# GR_Alim.net
KiCad netlist of a schematic drawn in Altium Designer
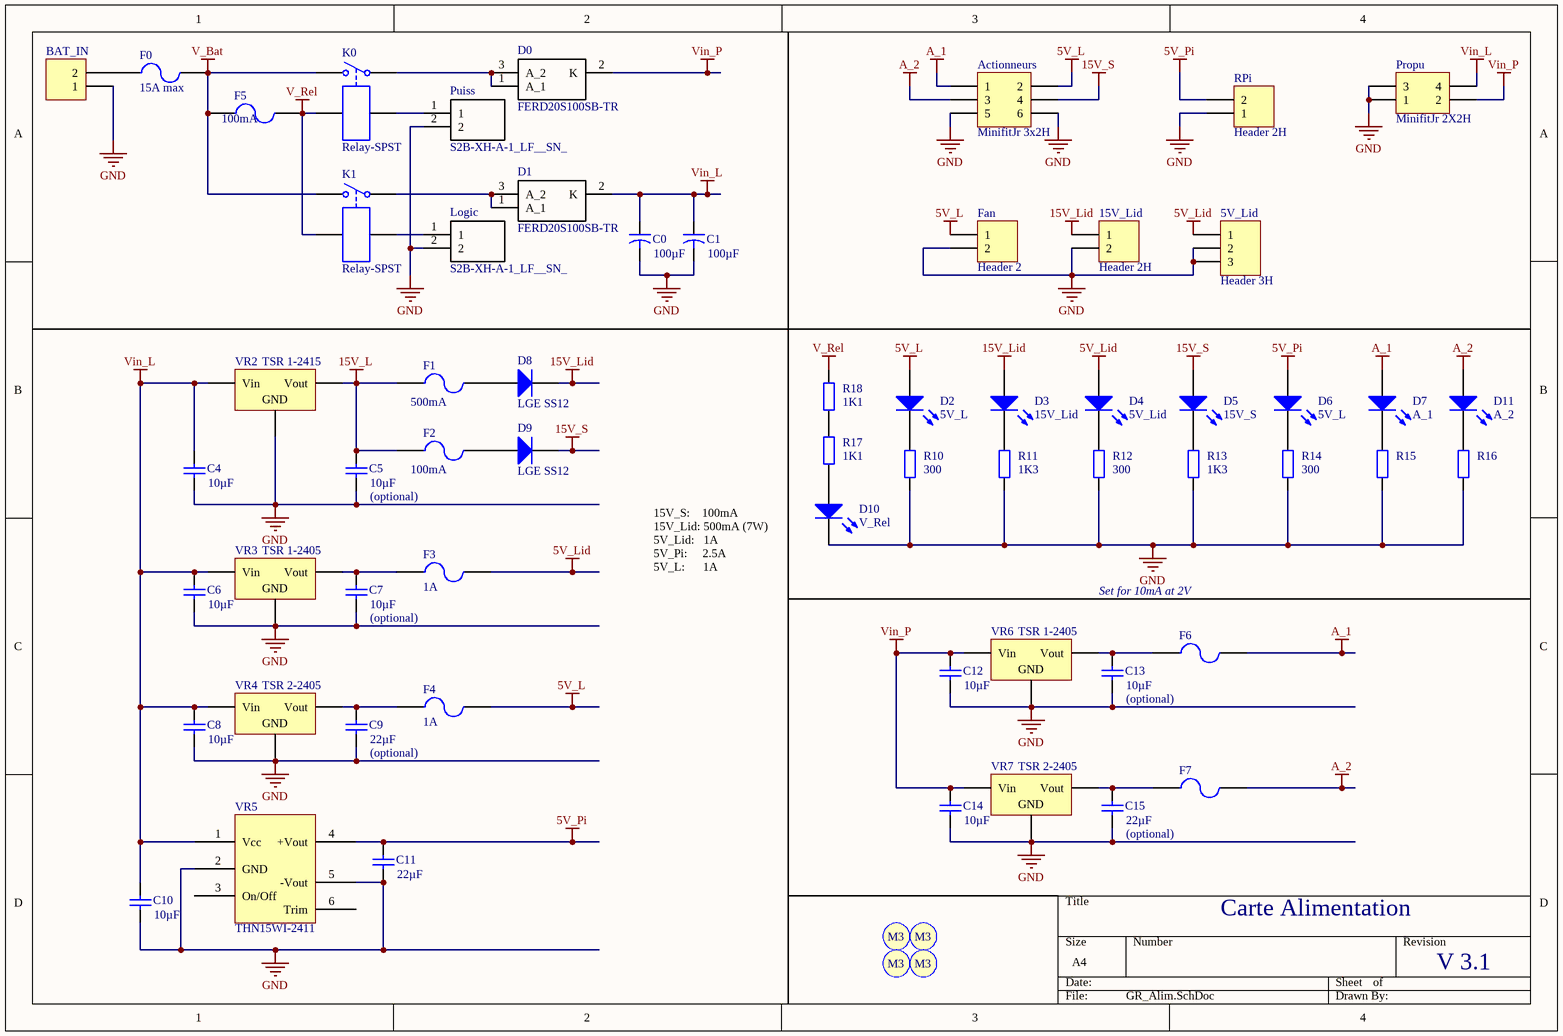
[diagram p0: GR_Alim.SchDoc]

(export (version "E")
  (design (tool "Eeschema 10.0.6"))
  (components
    (comp (ref "5V_Lid")
      (value "Header 3H")
      (footprint "S3B-XH-A")
      (description "Header, 3-Pin, Right Angle")
      (fields (field (name "PUBLISHER") "Altium Limited"))
      (libsource (lib "Miscellaneous Connectors") (part "Header 3H"))
    )
    (comp (ref "15V_Lid")
      (value "Header 2H")
      (footprint "S2B-XH-A")
      (description "Header, 2-Pin, Right Angle")
      (fields (field (name "PUBLISHER") "Altium Limited"))
      (libsource (lib "Miscellaneous Connectors") (part "Header 2H"))
    )
    (comp (ref "Actionneurs")
      (value "MinifitJr 3x2H")
      (footprint "MOLEX_MINIFITJR_3X2H")
      (description "Header, 3-Pin, Dual row, Right Angle")
      (fields (field (name "PUBLISHER") "Altium Limited"))
      (libsource (lib "Miscellaneous Connectors") (part "Header 3X2H"))
    )
    (comp (ref "BAT_IN")
      (value "Battery Onboard Solder")
      (footprint "Battery SALE")
      (description "Header, 2-Pin")
      (fields (field (name "PUBLISHER") "Altium Limited"))
      (libsource (lib "Miscellaneous Connectors") (part "Header 2"))
    )
    (comp (ref "C0")
      (value "100µF")
      (footprint "Condensateur")
      (description "Capacitor")
      (fields (field (name "Comment") "Cap2") (field (name "PUBLISHER") "Altium Limited"))
      (libsource (lib "Miscellaneous Devices") (part "Cap2"))
    )
    (comp (ref "C1")
      (value "100µF")
      (footprint "Condensateur")
      (description "Capacitor")
      (fields (field (name "Comment") "Cap2") (field (name "PUBLISHER") "Altium Limited"))
      (libsource (lib "Miscellaneous Devices") (part "Cap2"))
    )
    (comp (ref "C4")
      (value "10µF")
      (footprint "Capacitor 1206")
      (description "Capacitor")
      (fields (field (name "Comment") "Cap") (field (name "PUBLISHER") "Altium Limited"))
      (libsource (lib "Miscellaneous Devices") (part "Cap"))
    )
    (comp (ref "C5")
      (value "(optional)")
      (footprint "Capacitor 1206")
      (description "Capacitor")
      (fields (field (name "ALTIUM_VALUE") "10µF") (field (name "PUBLISHER") "Altium Limited"))
      (libsource (lib "Miscellaneous Devices") (part "Cap"))
    )
    (comp (ref "C6")
      (value "10µF")
      (footprint "Capacitor 1206")
      (description "Capacitor")
      (fields (field (name "Comment") "Cap") (field (name "PUBLISHER") "Altium Limited"))
      (libsource (lib "Miscellaneous Devices") (part "Cap"))
    )
    (comp (ref "C7")
      (value "(optional)")
      (footprint "Capacitor 1206")
      (description "Capacitor")
      (fields (field (name "ALTIUM_VALUE") "10µF") (field (name "PUBLISHER") "Altium Limited"))
      (libsource (lib "Miscellaneous Devices") (part "Cap"))
    )
    (comp (ref "C8")
      (value "10µF")
      (footprint "Capacitor 1206")
      (description "Capacitor")
      (fields (field (name "Comment") "Cap") (field (name "PUBLISHER") "Altium Limited"))
      (libsource (lib "Miscellaneous Devices") (part "Cap"))
    )
    (comp (ref "C9")
      (value "(optional)")
      (footprint "Capacitor 1206")
      (description "Capacitor")
      (fields (field (name "ALTIUM_VALUE") "22µF") (field (name "PUBLISHER") "Altium Limited"))
      (libsource (lib "Miscellaneous Devices") (part "Cap"))
    )
    (comp (ref "C10")
      (value "10µF")
      (footprint "Capacitor 1206")
      (description "Capacitor")
      (fields (field (name "Comment") "Cap") (field (name "PUBLISHER") "Altium Limited"))
      (libsource (lib "Miscellaneous Devices") (part "Cap"))
    )
    (comp (ref "C11")
      (value "22µF")
      (footprint "Capacitor 1206")
      (description "Capacitor")
      (fields (field (name "Comment") "Cap") (field (name "PUBLISHER") "Altium Limited"))
      (libsource (lib "Miscellaneous Devices") (part "Cap"))
    )
    (comp (ref "C12")
      (value "10µF")
      (footprint "Capacitor 1206")
      (description "Capacitor")
      (fields (field (name "Comment") "Cap") (field (name "PUBLISHER") "Altium Limited"))
      (libsource (lib "Miscellaneous Devices") (part "Cap"))
    )
    (comp (ref "C13")
      (value "(optional)")
      (footprint "Capacitor 1206")
      (description "Capacitor")
      (fields (field (name "ALTIUM_VALUE") "10µF") (field (name "PUBLISHER") "Altium Limited"))
      (libsource (lib "Miscellaneous Devices") (part "Cap"))
    )
    (comp (ref "C14")
      (value "10µF")
      (footprint "Capacitor 1206")
      (description "Capacitor")
      (fields (field (name "Comment") "Cap") (field (name "PUBLISHER") "Altium Limited"))
      (libsource (lib "Miscellaneous Devices") (part "Cap"))
    )
    (comp (ref "C15")
      (value "(optional)")
      (footprint "Capacitor 1206")
      (description "Capacitor")
      (fields (field (name "ALTIUM_VALUE") "22µF") (field (name "PUBLISHER") "Altium Limited"))
      (libsource (lib "Miscellaneous Devices") (part "Cap"))
    )
    (comp (ref "D0")
      (value "FERD20S100SB-TR")
      (footprint "SamacSys:FERD20H100SBTR")
      (description "Diode")
      (fields (field (name "MOUSER PART NUMBER") "511-FERD20S100SB-TR"))
      (libsource (lib "*") (part "FERD20S100SB-TR"))
    )
    (comp (ref "D1")
      (value "FERD20S100SB-TR")
      (footprint "SamacSys:FERD20H100SBTR")
      (description "Diode")
      (fields (field (name "MOUSER PART NUMBER") "511-FERD20S100SB-TR"))
      (libsource (lib "*") (part "FERD20S100SB-TR"))
    )
    (comp (ref "D2")
      (value "5V_L")
      (footprint "KP-3216SEC")
      (description "Typical RED, GREEN, YELLOW, AMBER GaAs LED")
      (fields (field (name "PUBLISHER") "Altium Limited"))
      (libsource (lib "Miscellaneous Devices") (part "LED2"))
    )
    (comp (ref "D3")
      (value "15V_Lid")
      (footprint "KP-3216SEC")
      (description "Typical RED, GREEN, YELLOW, AMBER GaAs LED")
      (fields (field (name "PUBLISHER") "Altium Limited"))
      (libsource (lib "Miscellaneous Devices") (part "LED2"))
    )
    (comp (ref "D4")
      (value "5V_Lid")
      (footprint "KP-3216SEC")
      (description "Typical RED, GREEN, YELLOW, AMBER GaAs LED")
      (fields (field (name "PUBLISHER") "Altium Limited"))
      (libsource (lib "Miscellaneous Devices") (part "LED2"))
    )
    (comp (ref "D5")
      (value "15V_S")
      (footprint "KP-3216SEC")
      (description "Typical RED, GREEN, YELLOW, AMBER GaAs LED")
      (fields (field (name "PUBLISHER") "Altium Limited"))
      (libsource (lib "Miscellaneous Devices") (part "LED2"))
    )
    (comp (ref "D6")
      (value "5V_L")
      (footprint "KP-3216SEC")
      (description "Typical RED, GREEN, YELLOW, AMBER GaAs LED")
      (fields (field (name "PUBLISHER") "Altium Limited"))
      (libsource (lib "Miscellaneous Devices") (part "LED2"))
    )
    (comp (ref "D7")
      (value "A_1")
      (footprint "KP-3216SEC")
      (description "Typical RED, GREEN, YELLOW, AMBER GaAs LED")
      (fields (field (name "PUBLISHER") "Altium Limited"))
      (libsource (lib "Miscellaneous Devices") (part "LED2"))
    )
    (comp (ref "D8")
      (value "LGE SS12")
      (footprint "SMB")
      (description "Default Diode")
      (fields (field (name "PUBLISHER") "Altium Limited"))
      (libsource (lib "Miscellaneous Devices") (part "Diode"))
    )
    (comp (ref "D9")
      (value "LGE SS12")
      (footprint "SMB")
      (description "Default Diode")
      (fields (field (name "PUBLISHER") "Altium Limited"))
      (libsource (lib "Miscellaneous Devices") (part "Diode"))
    )
    (comp (ref "D10")
      (value "V_Rel")
      (footprint "KP-3216SEC")
      (description "Typical RED, GREEN, YELLOW, AMBER GaAs LED")
      (fields (field (name "PUBLISHER") "Altium Limited"))
      (libsource (lib "Miscellaneous Devices") (part "LED2"))
    )
    (comp (ref "D11")
      (value "A_2")
      (footprint "KP-3216SEC")
      (description "Typical RED, GREEN, YELLOW, AMBER GaAs LED")
      (fields (field (name "PUBLISHER") "Altium Limited"))
      (libsource (lib "Miscellaneous Devices") (part "LED2"))
    )
    (comp (ref "F0")
      (value "15A max")
      (footprint "Fuse")
      (description "Main Fuse")
      (fields (field (name "PUBLISHER") "Altium Limited"))
      (libsource (lib "Miscellaneous Devices") (part "Fuse 2"))
    )
    (comp (ref "F1")
      (value "500mA")
      (footprint "3.5X2.8X1.9")
      (description "Fuse")
      (fields (field (name "PUBLISHER") "Altium Limited"))
      (libsource (lib "Miscellaneous Devices") (part "Fuse 2"))
    )
    (comp (ref "F2")
      (value "100mA")
      (footprint "3.5X2.8X1.9")
      (description "MICROSMD010F-2")
      (fields (field (name "PUBLISHER") "Altium Limited"))
      (libsource (lib "Miscellaneous Devices") (part "Fuse 2"))
    )
    (comp (ref "F3")
      (value "1A")
      (footprint "3.5X2.8X1.9")
      (description "Fuse")
      (fields (field (name "PUBLISHER") "Altium Limited"))
      (libsource (lib "Miscellaneous Devices") (part "Fuse 2"))
    )
    (comp (ref "F4")
      (value "1A")
      (footprint "3.5X2.8X1.9")
      (description "Fuse")
      (fields (field (name "PUBLISHER") "Altium Limited"))
      (libsource (lib "Miscellaneous Devices") (part "Fuse 2"))
    )
    (comp (ref "F5")
      (value "100mA")
      (footprint "3.5X2.8X1.9")
      (description "Fuse")
      (fields (field (name "PUBLISHER") "Altium Limited"))
      (libsource (lib "Miscellaneous Devices") (part "Fuse 2"))
    )
    (comp (ref "F6")
      (value "Fuse 2")
      (footprint "3.5X2.8X1.9")
      (description "Fuse")
      (fields (field (name "PUBLISHER") "Altium Limited"))
      (libsource (lib "Miscellaneous Devices") (part "Fuse 2"))
    )
    (comp (ref "F7")
      (value "Fuse 2")
      (footprint "3.5X2.8X1.9")
      (description "Fuse")
      (fields (field (name "PUBLISHER") "Altium Limited"))
      (libsource (lib "Miscellaneous Devices") (part "Fuse 2"))
    )
    (comp (ref "Fan")
      (value "Header 2")
      (footprint "HDR1X2")
      (description "Header, 2-Pin")
      (fields (field (name "PUBLISHER") "Altium Limited"))
      (libsource (lib "") (part "Header 2_1"))
    )
    (comp (ref "K0")
      (value "Relay-SPST")
      (footprint "Relay")
      (description "Single-Pole Single-Throw Relay")
      (fields (field (name "PUBLISHER") "Altium Limited"))
      (libsource (lib "Miscellaneous Devices") (part "Relay-SPST"))
    )
    (comp (ref "K1")
      (value "Relay-SPST")
      (footprint "Relay")
      (description "Single-Pole Single-Throw Relay")
      (fields (field (name "PUBLISHER") "Altium Limited"))
      (libsource (lib "Miscellaneous Devices") (part "Relay-SPST"))
    )
    (comp (ref "Logic")
      (value "S2B-XH-A-1_LF__SN_")
      (footprint "SamacSys:S2B-XH-A")
      (description "Connector")
      (fields (field (name "MANUFACTURER_PART_NUMBER") "S2B-XH-A-1(LF)(SN)"))
      (libsource (lib "SamacSys") (part "S2B-XH-A-1_LF__SN_"))
    )
    (comp (ref "Propu")
      (value "MinifitJr 2X2H")
      (footprint "MOLEX_MINIFITJR_2X2H")
      (description "Header, 2-Pin, Dual row, Right Angle")
      (fields (field (name "PUBLISHER") "Altium Limited"))
      (libsource (lib "Miscellaneous Connectors") (part "Header 2X2H"))
    )
    (comp (ref "Puiss")
      (value "S2B-XH-A-1_LF__SN_")
      (footprint "SamacSys:S2B-XH-A")
      (description "Connector")
      (fields (field (name "MANUFACTURER_PART_NUMBER") "S2B-XH-A-1(LF)(SN)"))
      (libsource (lib "SamacSys") (part "S2B-XH-A-1_LF__SN_"))
    )
    (comp (ref "R10")
      (value "300")
      (footprint "Resistor 1206")
      (description "Resistor")
      (fields (field (name "Comment") "Res2") (field (name "PUBLISHER") "Altium Limited"))
      (libsource (lib "") (part "Res2_1"))
    )
    (comp (ref "R11")
      (value "1K3")
      (footprint "Resistor 1206")
      (description "Resistor")
      (fields (field (name "Comment") "Res2") (field (name "PUBLISHER") "Altium Limited"))
      (libsource (lib "") (part "Res2_1"))
    )
    (comp (ref "R12")
      (value "300")
      (footprint "Resistor 1206")
      (description "Resistor")
      (fields (field (name "Comment") "Res2") (field (name "PUBLISHER") "Altium Limited"))
      (libsource (lib "") (part "Res2_1"))
    )
    (comp (ref "R13")
      (value "1K3")
      (footprint "Resistor 1206")
      (description "Resistor")
      (fields (field (name "Comment") "Res2") (field (name "PUBLISHER") "Altium Limited"))
      (libsource (lib "Miscellaneous Devices") (part "Res2"))
    )
    (comp (ref "R14")
      (value "300")
      (footprint "Resistor 1206")
      (description "Resistor")
      (fields (field (name "Comment") "Res2") (field (name "PUBLISHER") "Altium Limited"))
      (libsource (lib "Miscellaneous Devices") (part "Res2"))
    )
    (comp (ref "R15")
      (value "Res2")
      (footprint "Resistor 1206")
      (description "Resistor")
      (fields (field (name "PUBLISHER") "Altium Limited"))
      (libsource (lib "Miscellaneous Devices") (part "Res2"))
    )
    (comp (ref "R16")
      (value "Res2")
      (footprint "Resistor 1206")
      (description "Resistor")
      (fields (field (name "PUBLISHER") "Altium Limited"))
      (libsource (lib "Miscellaneous Devices") (part "Res2"))
    )
    (comp (ref "R17")
      (value "1K1")
      (footprint "Resistor 1206")
      (description "Resistor")
      (fields (field (name "Comment") "Res2") (field (name "PUBLISHER") "Altium Limited"))
      (libsource (lib "Miscellaneous Devices") (part "Res2"))
    )
    (comp (ref "R18")
      (value "1K1")
      (footprint "Resistor 1206")
      (description "Resistor")
      (fields (field (name "Comment") "Res2") (field (name "PUBLISHER") "Altium Limited"))
      (libsource (lib "Miscellaneous Devices") (part "Res2"))
    )
    (comp (ref "RPi")
      (value "Header 2H")
      (footprint "Molex_MiniFitJr_2x1H")
      (description "Header, 2-Pin, Right Angle")
      (fields (field (name "PUBLISHER") "Altium Limited"))
      (libsource (lib "") (part "Header 2H_1"))
    )
    (comp (ref "S1")
      (value "Screw M3")
      (footprint "Screw M3")
      (libsource (lib "Robot_2020") (part "Screw M3"))
    )
    (comp (ref "S2")
      (value "Screw M3")
      (footprint "Screw M3")
      (libsource (lib "Robot_2020") (part "Screw M3"))
    )
    (comp (ref "S3")
      (value "Screw M3")
      (footprint "Screw M3")
      (libsource (lib "Robot_2020") (part "Screw M3"))
    )
    (comp (ref "S4")
      (value "Screw M3")
      (footprint "Screw M3")
      (libsource (lib "Robot_2020") (part "Screw M3"))
    )
    (comp (ref "VR2")
      (value "TSR 1-2415")
      (footprint "TRS - Both")
      (description "Voltage Regulator")
      (fields (field (name "PUBLISHER") "Altium Limited"))
      (libsource (lib "Miscellaneous Devices") (part "Volt Reg"))
    )
    (comp (ref "VR3")
      (value "TSR 1-2405")
      (footprint "TRS - Both")
      (description "Voltage Regulator")
      (fields (field (name "PUBLISHER") "Altium Limited"))
      (libsource (lib "Miscellaneous Devices") (part "Volt Reg"))
    )
    (comp (ref "VR4")
      (value "TSR 2-2405")
      (footprint "TRS - Both")
      (description "Voltage Regulator")
      (fields (field (name "PUBLISHER") "Altium Limited"))
      (libsource (lib "Miscellaneous Devices") (part "Volt Reg"))
    )
    (comp (ref "VR5")
      (value "THN15WI-2411")
      (footprint "TRACO_1x1inch")
      (description "TRACO THN15WI-2411")
      (fields (field (name "PUBLISHER") "Altium Limited"))
      (libsource (lib "Robot_2020") (part "TEN60N"))
    )
    (comp (ref "VR6")
      (value "TSR 1-2405")
      (footprint "TRS - Both")
      (description "Voltage Regulator")
      (fields (field (name "PUBLISHER") "Altium Limited"))
      (libsource (lib "Miscellaneous Devices") (part "Volt Reg"))
    )
    (comp (ref "VR7")
      (value "TSR 2-2405")
      (footprint "TRS - Both")
      (description "Voltage Regulator")
      (fields (field (name "PUBLISHER") "Altium Limited"))
      (libsource (lib "Miscellaneous Devices") (part "Volt Reg"))
    )
  )
  (nets
    (net (code "1") (name "5V_L") (class "Default")
      (node (ref "Actionneurs") (pin "2") (pinfunction "2_2") (pintype "passive"))
      (node (ref "D2") (pin "1") (pinfunction "A_1") (pintype "passive"))
      (node (ref "F4") (pin "2") (pinfunction "2_2") (pintype "passive"))
      (node (ref "Fan") (pin "1") (pinfunction "1_1") (pintype "passive"))
    )
    (net (code "2") (name "5V_Lid") (class "Default")
      (node (ref "5V_Lid") (pin "1") (pinfunction "1_1") (pintype "passive"))
      (node (ref "D4") (pin "1") (pinfunction "A_1") (pintype "passive"))
      (node (ref "F3") (pin "2") (pinfunction "2_2") (pintype "passive"))
    )
    (net (code "3") (name "5V_Pi") (class "Default")
      (node (ref "C11") (pin "2") (pinfunction "2_2") (pintype "passive"))
      (node (ref "D6") (pin "1") (pinfunction "A_1") (pintype "passive"))
      (node (ref "RPi") (pin "2") (pinfunction "2_2") (pintype "passive"))
      (node (ref "VR5") (pin "4") (pinfunction "+Vout_4") (pintype "passive"))
    )
    (net (code "4") (name "15V_L") (class "Default")
      (node (ref "C5") (pin "2") (pinfunction "2_2") (pintype "passive"))
      (node (ref "F1") (pin "1") (pinfunction "1_1") (pintype "passive"))
      (node (ref "F2") (pin "1") (pinfunction "1_1") (pintype "passive"))
      (node (ref "VR2") (pin "3") (pinfunction "Vout_3") (pintype "passive"))
    )
    (net (code "5") (name "15V_Lid") (class "Default")
      (node (ref "15V_Lid") (pin "1") (pinfunction "1_1") (pintype "passive"))
      (node (ref "D3") (pin "1") (pinfunction "A_1") (pintype "passive"))
      (node (ref "D8") (pin "2") (pinfunction "K_2") (pintype "passive"))
    )
    (net (code "6") (name "15V_S") (class "Default")
      (node (ref "Actionneurs") (pin "4") (pinfunction "4_4") (pintype "passive"))
      (node (ref "D5") (pin "1") (pinfunction "A_1") (pintype "passive"))
      (node (ref "D9") (pin "2") (pinfunction "K_2") (pintype "passive"))
    )
    (net (code "7") (name "A_1") (class "Default")
      (node (ref "Actionneurs") (pin "1") (pinfunction "1_1") (pintype "passive"))
      (node (ref "D7") (pin "1") (pinfunction "A_1") (pintype "passive"))
      (node (ref "F6") (pin "2") (pinfunction "2_2") (pintype "passive"))
    )
    (net (code "8") (name "A_2") (class "Default")
      (node (ref "Actionneurs") (pin "3") (pinfunction "3_3") (pintype "passive"))
      (node (ref "D11") (pin "1") (pinfunction "A_1") (pintype "passive"))
      (node (ref "F7") (pin "2") (pinfunction "2_2") (pintype "passive"))
    )
    (net (code "9") (name "GND") (class "Default")
      (node (ref "15V_Lid") (pin "2") (pinfunction "2_2") (pintype "passive"))
      (node (ref "5V_Lid") (pin "2") (pinfunction "2_2") (pintype "passive"))
      (node (ref "5V_Lid") (pin "3") (pinfunction "3_3") (pintype "passive"))
      (node (ref "Actionneurs") (pin "5") (pinfunction "5_5") (pintype "passive"))
      (node (ref "Actionneurs") (pin "6") (pinfunction "6_6") (pintype "passive"))
      (node (ref "BAT_IN") (pin "1") (pinfunction "1_1") (pintype "passive"))
      (node (ref "C0") (pin "2") (pinfunction "2_2") (pintype "passive"))
      (node (ref "C1") (pin "2") (pinfunction "2_2") (pintype "passive"))
      (node (ref "C10") (pin "1") (pinfunction "1_1") (pintype "passive"))
      (node (ref "C11") (pin "1") (pinfunction "1_1") (pintype "passive"))
      (node (ref "C12") (pin "1") (pinfunction "1_1") (pintype "passive"))
      (node (ref "C13") (pin "1") (pinfunction "1_1") (pintype "passive"))
      (node (ref "C14") (pin "1") (pinfunction "1_1") (pintype "passive"))
      (node (ref "C15") (pin "1") (pinfunction "1_1") (pintype "passive"))
      (node (ref "C4") (pin "1") (pinfunction "1_1") (pintype "passive"))
      (node (ref "C5") (pin "1") (pinfunction "1_1") (pintype "passive"))
      (node (ref "C6") (pin "1") (pinfunction "1_1") (pintype "passive"))
      (node (ref "C7") (pin "1") (pinfunction "1_1") (pintype "passive"))
      (node (ref "C8") (pin "1") (pinfunction "1_1") (pintype "passive"))
      (node (ref "C9") (pin "1") (pinfunction "1_1") (pintype "passive"))
      (node (ref "D10") (pin "2") (pinfunction "K_2") (pintype "passive"))
      (node (ref "Fan") (pin "2") (pinfunction "2_2") (pintype "passive"))
      (node (ref "Logic") (pin "2") (pinfunction "2_2") (pintype "passive"))
      (node (ref "Propu") (pin "1") (pinfunction "1_1") (pintype "passive"))
      (node (ref "Propu") (pin "3") (pinfunction "3_3") (pintype "passive"))
      (node (ref "Puiss") (pin "2") (pinfunction "2_2") (pintype "passive"))
      (node (ref "R10") (pin "1") (pinfunction "1_1") (pintype "passive"))
      (node (ref "R11") (pin "1") (pinfunction "1_1") (pintype "passive"))
      (node (ref "R12") (pin "1") (pinfunction "1_1") (pintype "passive"))
      (node (ref "R13") (pin "2") (pinfunction "2_2") (pintype "passive"))
      (node (ref "R14") (pin "2") (pinfunction "2_2") (pintype "passive"))
      (node (ref "R15") (pin "2") (pinfunction "2_2") (pintype "passive"))
      (node (ref "R16") (pin "2") (pinfunction "2_2") (pintype "passive"))
      (node (ref "RPi") (pin "1") (pinfunction "1_1") (pintype "passive"))
      (node (ref "VR2") (pin "2") (pinfunction "GND_2") (pintype "passive"))
      (node (ref "VR3") (pin "2") (pinfunction "GND_2") (pintype "passive"))
      (node (ref "VR4") (pin "2") (pinfunction "GND_2") (pintype "passive"))
      (node (ref "VR5") (pin "2") (pinfunction "GND_2") (pintype "passive"))
      (node (ref "VR5") (pin "5") (pinfunction "-Vout_5") (pintype "passive"))
      (node (ref "VR6") (pin "2") (pinfunction "GND_2") (pintype "passive"))
      (node (ref "VR7") (pin "2") (pinfunction "GND_2") (pintype "passive"))
    )
    (net (code "10") (name "Net-(BAT_IN-Pad2)") (class "Default")
      (node (ref "BAT_IN") (pin "2") (pinfunction "2_2") (pintype "passive"))
      (node (ref "F0") (pin "1") (pinfunction "1_1") (pintype "passive"))
    )
    (net (code "11") (name "Net-(D0-A_1)") (class "Default")
      (node (ref "D0") (pin "1") (pinfunction "A_1_1") (pintype "passive"))
      (node (ref "D0") (pin "3") (pinfunction "A_2_3") (pintype "passive"))
      (node (ref "K0") (pin "1") (pinfunction "1_1") (pintype "passive"))
    )
    (net (code "12") (name "Net-(D1-A_1)") (class "Default")
      (node (ref "D1") (pin "1") (pinfunction "A_1_1") (pintype "passive"))
      (node (ref "D1") (pin "3") (pinfunction "A_2_3") (pintype "passive"))
      (node (ref "K1") (pin "1") (pinfunction "1_1") (pintype "passive"))
    )
    (net (code "13") (name "Net-(D2-K)") (class "Default")
      (node (ref "D2") (pin "2") (pinfunction "K_2") (pintype "passive"))
      (node (ref "R10") (pin "2") (pinfunction "2_2") (pintype "passive"))
    )
    (net (code "14") (name "Net-(D3-K)") (class "Default")
      (node (ref "D3") (pin "2") (pinfunction "K_2") (pintype "passive"))
      (node (ref "R11") (pin "2") (pinfunction "2_2") (pintype "passive"))
    )
    (net (code "15") (name "Net-(D4-K)") (class "Default")
      (node (ref "D4") (pin "2") (pinfunction "K_2") (pintype "passive"))
      (node (ref "R12") (pin "2") (pinfunction "2_2") (pintype "passive"))
    )
    (net (code "16") (name "Net-(D5-K)") (class "Default")
      (node (ref "D5") (pin "2") (pinfunction "K_2") (pintype "passive"))
      (node (ref "R13") (pin "1") (pinfunction "1_1") (pintype "passive"))
    )
    (net (code "17") (name "Net-(D6-K)") (class "Default")
      (node (ref "D6") (pin "2") (pinfunction "K_2") (pintype "passive"))
      (node (ref "R14") (pin "1") (pinfunction "1_1") (pintype "passive"))
    )
    (net (code "18") (name "Net-(D7-K)") (class "Default")
      (node (ref "D7") (pin "2") (pinfunction "K_2") (pintype "passive"))
      (node (ref "R15") (pin "1") (pinfunction "1_1") (pintype "passive"))
    )
    (net (code "19") (name "Net-(D8-A)") (class "Default")
      (node (ref "D8") (pin "1") (pinfunction "A_1") (pintype "passive"))
      (node (ref "F1") (pin "2") (pinfunction "2_2") (pintype "passive"))
    )
    (net (code "20") (name "Net-(D9-A)") (class "Default")
      (node (ref "D9") (pin "1") (pinfunction "A_1") (pintype "passive"))
      (node (ref "F2") (pin "2") (pinfunction "2_2") (pintype "passive"))
    )
    (net (code "21") (name "Net-(D10-A)") (class "Default")
      (node (ref "D10") (pin "1") (pinfunction "A_1") (pintype "passive"))
      (node (ref "R17") (pin "2") (pinfunction "2_2") (pintype "passive"))
    )
    (net (code "22") (name "Net-(D11-K)") (class "Default")
      (node (ref "D11") (pin "2") (pinfunction "K_2") (pintype "passive"))
      (node (ref "R16") (pin "1") (pinfunction "1_1") (pintype "passive"))
    )
    (net (code "23") (name "Net-(K0-Pad3)") (class "Default")
      (node (ref "K0") (pin "3") (pinfunction "3_3") (pintype "passive"))
      (node (ref "Puiss") (pin "1") (pinfunction "1_1") (pintype "passive"))
    )
    (net (code "24") (name "Net-(K1-Pad3)") (class "Default")
      (node (ref "K1") (pin "3") (pinfunction "3_3") (pintype "passive"))
      (node (ref "Logic") (pin "1") (pinfunction "1_1") (pintype "passive"))
    )
    (net (code "25") (name "Net-(R17-Pad1)") (class "Default")
      (node (ref "R17") (pin "1") (pinfunction "1_1") (pintype "passive"))
      (node (ref "R18") (pin "2") (pinfunction "2_2") (pintype "passive"))
    )
    (net (code "26") (name "Net-(VR3-Vout)") (class "Default")
      (node (ref "C7") (pin "2") (pinfunction "2_2") (pintype "passive"))
      (node (ref "F3") (pin "1") (pinfunction "1_1") (pintype "passive"))
      (node (ref "VR3") (pin "3") (pinfunction "Vout_3") (pintype "passive"))
    )
    (net (code "27") (name "Net-(VR4-Vout)") (class "Default")
      (node (ref "C9") (pin "2") (pinfunction "2_2") (pintype "passive"))
      (node (ref "F4") (pin "1") (pinfunction "1_1") (pintype "passive"))
      (node (ref "VR4") (pin "3") (pinfunction "Vout_3") (pintype "passive"))
    )
    (net (code "28") (name "Net-(VR6-Vout)") (class "Default")
      (node (ref "C13") (pin "2") (pinfunction "2_2") (pintype "passive"))
      (node (ref "F6") (pin "1") (pinfunction "1_1") (pintype "passive"))
      (node (ref "VR6") (pin "3") (pinfunction "Vout_3") (pintype "passive"))
    )
    (net (code "29") (name "Net-(VR7-Vout)") (class "Default")
      (node (ref "C15") (pin "2") (pinfunction "2_2") (pintype "passive"))
      (node (ref "F7") (pin "1") (pinfunction "1_1") (pintype "passive"))
      (node (ref "VR7") (pin "3") (pinfunction "Vout_3") (pintype "passive"))
    )
    (net (code "30") (name "V_Bat") (class "Default")
      (node (ref "F0") (pin "2") (pinfunction "2_2") (pintype "passive"))
      (node (ref "F5") (pin "1") (pinfunction "1_1") (pintype "passive"))
      (node (ref "K0") (pin "2") (pinfunction "2_2") (pintype "passive"))
      (node (ref "K1") (pin "2") (pinfunction "2_2") (pintype "passive"))
    )
    (net (code "31") (name "V_Rel") (class "Default")
      (node (ref "F5") (pin "2") (pinfunction "2_2") (pintype "passive"))
      (node (ref "K0") (pin "4") (pinfunction "4_4") (pintype "passive"))
      (node (ref "K1") (pin "4") (pinfunction "4_4") (pintype "passive"))
      (node (ref "R18") (pin "1") (pinfunction "1_1") (pintype "passive"))
    )
    (net (code "32") (name "Vin_L") (class "Default")
      (node (ref "C0") (pin "1") (pinfunction "1_1") (pintype "passive"))
      (node (ref "C1") (pin "1") (pinfunction "1_1") (pintype "passive"))
      (node (ref "C10") (pin "2") (pinfunction "2_2") (pintype "passive"))
      (node (ref "C4") (pin "2") (pinfunction "2_2") (pintype "passive"))
      (node (ref "C6") (pin "2") (pinfunction "2_2") (pintype "passive"))
      (node (ref "C8") (pin "2") (pinfunction "2_2") (pintype "passive"))
      (node (ref "D1") (pin "2") (pinfunction "K_2") (pintype "passive"))
      (node (ref "Propu") (pin "4") (pinfunction "4_4") (pintype "passive"))
      (node (ref "VR2") (pin "1") (pinfunction "Vin_1") (pintype "passive"))
      (node (ref "VR3") (pin "1") (pinfunction "Vin_1") (pintype "passive"))
      (node (ref "VR4") (pin "1") (pinfunction "Vin_1") (pintype "passive"))
      (node (ref "VR5") (pin "1") (pinfunction "Vcc_1") (pintype "passive"))
    )
    (net (code "33") (name "Vin_P") (class "Default")
      (node (ref "C12") (pin "2") (pinfunction "2_2") (pintype "passive"))
      (node (ref "C14") (pin "2") (pinfunction "2_2") (pintype "passive"))
      (node (ref "D0") (pin "2") (pinfunction "K_2") (pintype "passive"))
      (node (ref "Propu") (pin "2") (pinfunction "2_2") (pintype "passive"))
      (node (ref "VR6") (pin "1") (pinfunction "Vin_1") (pintype "passive"))
      (node (ref "VR7") (pin "1") (pinfunction "Vin_1") (pintype "passive"))
    )
    (net (code "34") (name "unconnected-(VR5-On{slash}Off-Pad3)") (class "Default")
      (node (ref "VR5") (pin "3") (pinfunction "On/Off_3") (pintype "passive"))
    )
    (net (code "35") (name "unconnected-(VR5-Trim-Pad6)") (class "Default")
      (node (ref "VR5") (pin "6") (pinfunction "Trim_6") (pintype "passive"))
    )
  )
)
